# wallplug.net
KiCad netlist of a schematic drawn in EAGLE
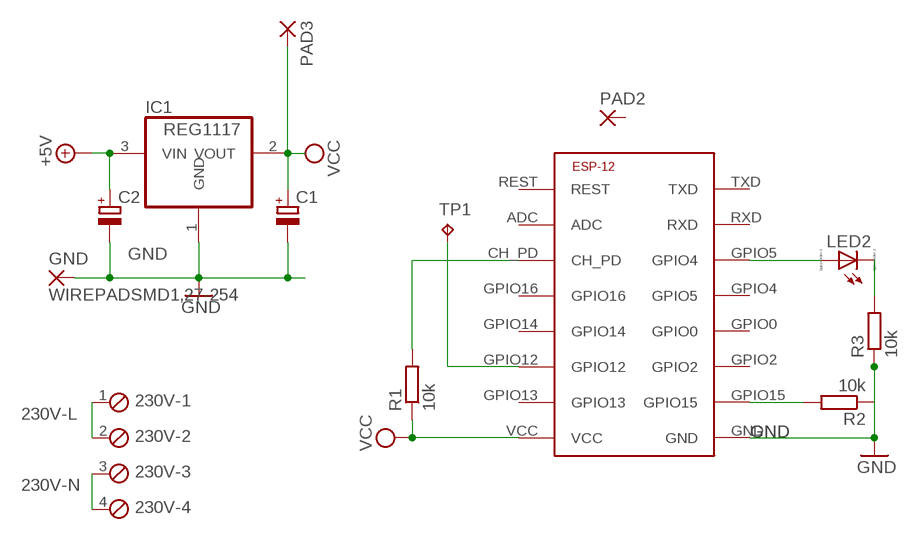
[diagram p0: schematic, sheet 1]

(export (version "E")
  (design (tool "Eeschema 10.0.6"))
  (components
    (comp (ref "230V")
      (value "MPT4")
      (footprint "eagle-import:4POL254")
      (libsource (lib "eagle-import") (part "MPT4"))
    )
    (comp (ref "C1")
      (value "CPOL-EUSMCC")
      (footprint "eagle-import:SMC_C")
      (libsource (lib "eagle-import") (part "CPOL-EUSMCC"))
    )
    (comp (ref "C2")
      (value "CPOL-EUSMCC")
      (footprint "eagle-import:SMC_C")
      (libsource (lib "eagle-import") (part "CPOL-EUSMCC"))
    )
    (comp (ref "ESP1")
      (value "ESP-12ESP-12")
      (footprint "eagle-import:ESP-12")
      (libsource (lib "eagle-import") (part "ESP-12ESP-12"))
    )
    (comp (ref "GND")
      (value "WIREPADSMD1,27-254")
      (footprint "eagle-import:SMD1,27-2,54")
      (libsource (lib "eagle-import") (part "WIREPADSMD1,27-254"))
    )
    (comp (ref "IC1")
      (value "REG1117")
      (footprint "eagle-import:SOT223")
      (fields (field (name "MF") "TEXAS INSTRUMENTS"))
      (libsource (lib "eagle-import") (part "REG1117"))
    )
    (comp (ref "LED2")
      (value "LED_ESML0603")
      (footprint "eagle-import:LED_SML0603")
      (libsource (lib "eagle-import") (part "LED_ESML0603"))
    )
    (comp (ref "PAD2")
      (value "1,6/0,9")
      (footprint "eagle-import:1,6_0,9")
      (libsource (lib "eagle-import") (part "1,6/0,9"))
    )
    (comp (ref "PAD3")
      (value "SMD5")
      (footprint "eagle-import:SMD2,54-5,08")
      (libsource (lib "eagle-import") (part "SMD5"))
    )
    (comp (ref "R1")
      (value "10k")
      (footprint "eagle-import:M0805")
      (fields (field (name "MF") "STMICROELECTRONICS") (field (name "MPN") "LD1117S33TR"))
      (libsource (lib "eagle-import") (part "R-EU_M0805"))
    )
    (comp (ref "R2")
      (value "10k")
      (footprint "eagle-import:M0805")
      (fields (field (name "MF") "STMICROELECTRONICS") (field (name "MPN") "LD1117S33TR"))
      (libsource (lib "eagle-import") (part "R-EU_M0805"))
    )
    (comp (ref "R3")
      (value "10k")
      (footprint "eagle-import:M0805")
      (fields (field (name "MF") "STMICROELECTRONICS") (field (name "MPN") "LD1117S33TR"))
      (libsource (lib "eagle-import") (part "R-EU_M0805"))
    )
    (comp (ref "TP1")
      (value "TPB1,27")
      (footprint "eagle-import:B1,27")
      (libsource (lib "eagle-import") (part "TPB1,27"))
    )
  )
  (nets
    (net (code "1") (name "+5V") (class "Default")
      (node (ref "C2") (pin "+") (pinfunction "+_+") (pintype "passive"))
      (node (ref "IC1") (pin "3") (pinfunction "VIN_3") (pintype "input"))
    )
    (net (code "2") (name "/230V-L") (class "Default")
      (node (ref "230V") (pin "1") (pinfunction "1_1") (pintype "passive"))
      (node (ref "230V") (pin "2") (pinfunction "1_2") (pintype "passive"))
    )
    (net (code "3") (name "/230V-N") (class "Default")
      (node (ref "230V") (pin "3") (pinfunction "1_3") (pintype "passive"))
      (node (ref "230V") (pin "4") (pinfunction "1_4") (pintype "passive"))
    )
    (net (code "4") (name "GND") (class "Default")
      (node (ref "C1") (pin "-") (pinfunction "-_-") (pintype "passive"))
      (node (ref "C2") (pin "-") (pinfunction "-_-") (pintype "passive"))
      (node (ref "ESP1") (pin "GND") (pinfunction "GND_GND") (pintype "bidirectional"))
      (node (ref "GND") (pin "1") (pinfunction "P_1") (pintype "passive"))
      (node (ref "IC1") (pin "1") (pinfunction "GND_1") (pintype "power_in"))
      (node (ref "R2") (pin "1") (pinfunction "1_1") (pintype "passive"))
      (node (ref "R3") (pin "1") (pinfunction "1_1") (pintype "passive"))
    )
    (net (code "5") (name "Net-(ESP1-GPIO4)") (class "Default")
      (node (ref "ESP1") (pin "GPIO5") (pinfunction "GPIO4_GPIO5") (pintype "bidirectional"))
      (node (ref "LED2") (pin "A") (pinfunction "A_A") (pintype "passive"))
    )
    (net (code "6") (name "Net-(ESP1-PadCH_PD)") (class "Default")
      (node (ref "ESP1") (pin "CH_PD") (pinfunction "CH_PD_CH_PD") (pintype "bidirectional"))
      (node (ref "R1") (pin "2") (pinfunction "2_2") (pintype "passive"))
    )
    (net (code "7") (name "Net-(ESP1-PadGPIO12)") (class "Default")
      (node (ref "ESP1") (pin "GPIO12") (pinfunction "GPIO12_GPIO12") (pintype "bidirectional"))
      (node (ref "TP1") (pin "TP") (pinfunction "TP_TP") (pintype "input"))
    )
    (net (code "8") (name "Net-(ESP1-PadGPIO15)") (class "Default")
      (node (ref "ESP1") (pin "GPIO15") (pinfunction "GPIO15_GPIO15") (pintype "bidirectional"))
      (node (ref "R2") (pin "2") (pinfunction "2_2") (pintype "passive"))
    )
    (net (code "9") (name "Net-(LED2-PadC)") (class "Default")
      (node (ref "LED2") (pin "C") (pinfunction "C_C") (pintype "passive"))
      (node (ref "R3") (pin "2") (pinfunction "2_2") (pintype "passive"))
    )
    (net (code "10") (name "VCC") (class "Default")
      (node (ref "C1") (pin "+") (pinfunction "+_+") (pintype "passive"))
      (node (ref "ESP1") (pin "VCC") (pinfunction "VCC_VCC") (pintype "bidirectional"))
      (node (ref "IC1") (pin "2") (pinfunction "VOUT_2") (pintype "output"))
      (node (ref "PAD3") (pin "1") (pinfunction "P_1") (pintype "passive"))
      (node (ref "R1") (pin "1") (pinfunction "1_1") (pintype "passive"))
    )
    (net (code "11") (name "unconnected-(ESP1-GPIO5-PadGPIO4)") (class "Default")
      (node (ref "ESP1") (pin "GPIO4") (pinfunction "GPIO5_GPIO4") (pintype "bidirectional"))
    )
    (net (code "12") (name "unconnected-(ESP1-PadADC)") (class "Default")
      (node (ref "ESP1") (pin "ADC") (pinfunction "ADC_ADC") (pintype "bidirectional"))
    )
    (net (code "13") (name "unconnected-(ESP1-PadGPIO0)") (class "Default")
      (node (ref "ESP1") (pin "GPIO0") (pinfunction "GPIO0_GPIO0") (pintype "bidirectional"))
    )
    (net (code "14") (name "unconnected-(ESP1-PadGPIO2)") (class "Default")
      (node (ref "ESP1") (pin "GPIO2") (pinfunction "GPIO2_GPIO2") (pintype "bidirectional"))
    )
    (net (code "15") (name "unconnected-(ESP1-PadGPIO13)") (class "Default")
      (node (ref "ESP1") (pin "GPIO13") (pinfunction "GPIO13_GPIO13") (pintype "bidirectional"))
    )
    (net (code "16") (name "unconnected-(ESP1-PadGPIO14)") (class "Default")
      (node (ref "ESP1") (pin "GPIO14") (pinfunction "GPIO14_GPIO14") (pintype "bidirectional"))
    )
    (net (code "17") (name "unconnected-(ESP1-PadGPIO16)") (class "Default")
      (node (ref "ESP1") (pin "GPIO16") (pinfunction "GPIO16_GPIO16") (pintype "bidirectional"))
    )
    (net (code "18") (name "unconnected-(ESP1-PadREST)") (class "Default")
      (node (ref "ESP1") (pin "REST") (pinfunction "REST_REST") (pintype "bidirectional"))
    )
    (net (code "19") (name "unconnected-(ESP1-PadRXD)") (class "Default")
      (node (ref "ESP1") (pin "RXD") (pinfunction "RXD_RXD") (pintype "bidirectional"))
    )
    (net (code "20") (name "unconnected-(ESP1-PadTXD)") (class "Default")
      (node (ref "ESP1") (pin "TXD") (pinfunction "TXD_TXD") (pintype "bidirectional"))
    )
    (net (code "21") (name "unconnected-(PAD2-P-Pad1)") (class "Default")
      (node (ref "PAD2") (pin "1") (pinfunction "P_1") (pintype "passive"))
    )
  )
)
